# DeepReset2.net
KiCad netlist of a schematic drawn in EAGLE
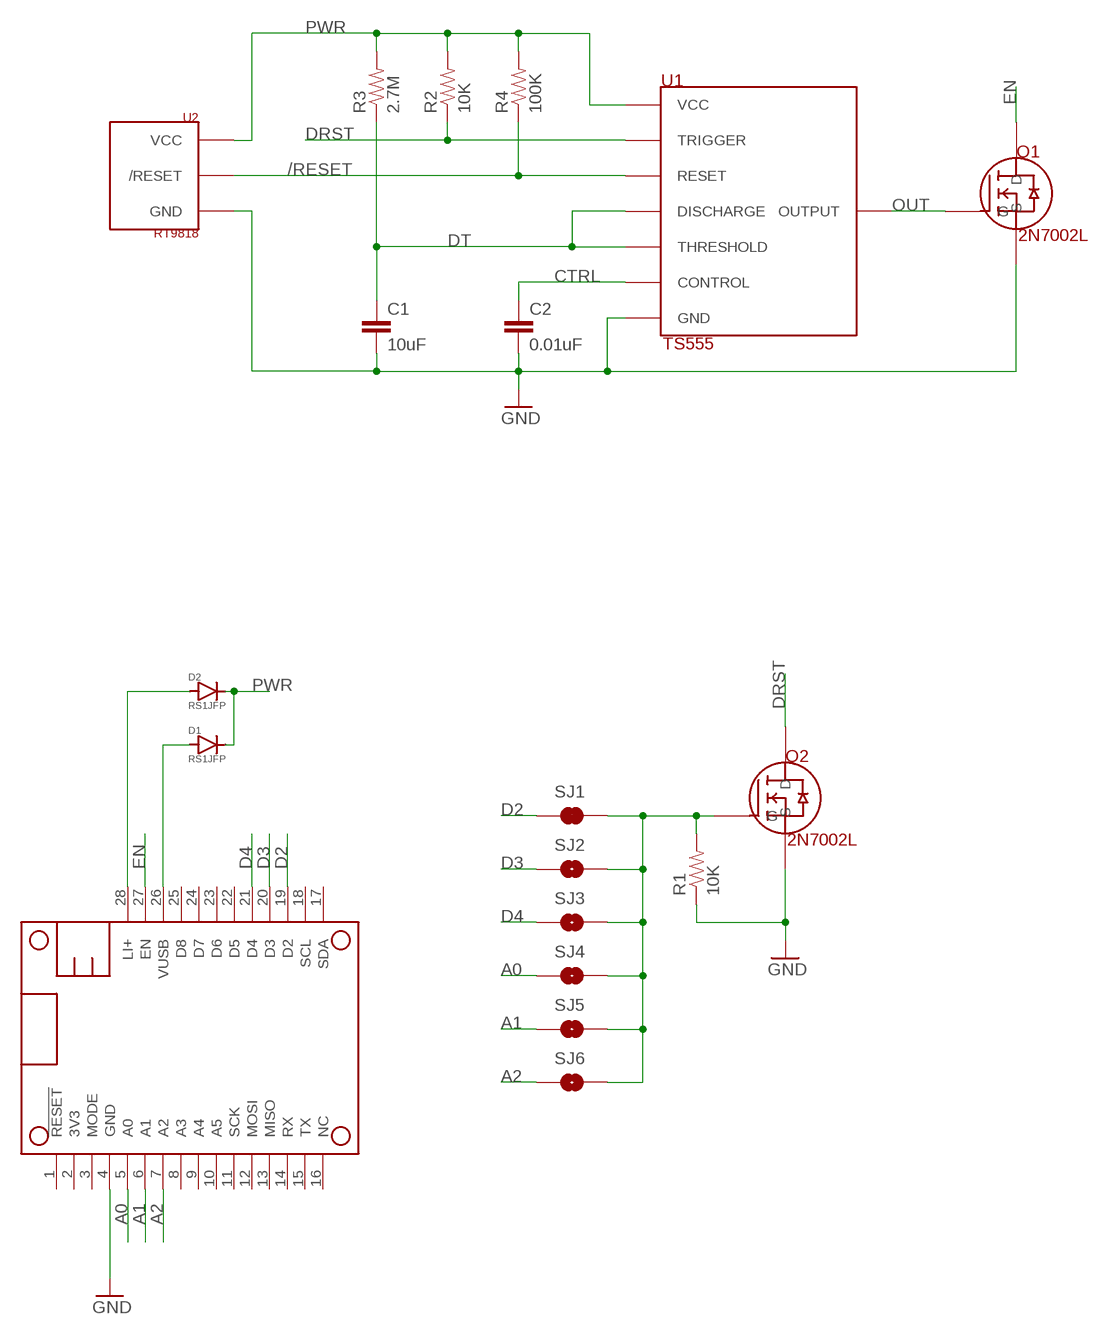
[diagram p0: schematic, sheet 1]

(export (version "E")
  (design (tool "Eeschema 10.0.6"))
  (components
    (comp (ref "C1")
      (value "10uF")
      (footprint "eagle-import:0603-CAP")
      (libsource (lib "eagle-import") (part "CAP-10UF-0603"))
    )
    (comp (ref "C2")
      (value "0.01uF")
      (footprint "eagle-import:0603-CAP")
      (libsource (lib "eagle-import") (part "CAP-0.01UF-0603"))
    )
    (comp (ref "D1")
      (value "RS1JFP")
      (footprint "eagle-import:SOD-123HE-ON")
      (libsource (lib "eagle-import") (part "DIODE-RS1JFP"))
    )
    (comp (ref "D2")
      (value "RS1JFP")
      (footprint "eagle-import:SOD-123HE-ON")
      (libsource (lib "eagle-import") (part "DIODE-RS1JFP"))
    )
    (comp (ref "MS1")
      (value "FEATHERWING_NODIM")
      (footprint "eagle-import:FEATHERWING_NODIM")
      (libsource (lib "eagle-import") (part "FEATHERWING_NODIM"))
    )
    (comp (ref "Q1")
      (value "2N7002L")
      (footprint "eagle-import:2N7002L")
      (libsource (lib "eagle-import") (part "2N7002L"))
    )
    (comp (ref "Q2")
      (value "2N7002L")
      (footprint "eagle-import:2N7002L")
      (libsource (lib "eagle-import") (part "2N7002L"))
    )
    (comp (ref "R1")
      (value "10K")
      (footprint "eagle-import:0603-RES")
      (libsource (lib "eagle-import") (part "RES-10K-06030603"))
    )
    (comp (ref "R2")
      (value "10K")
      (footprint "eagle-import:0603-RES")
      (libsource (lib "eagle-import") (part "RES-10K-06030603"))
    )
    (comp (ref "R3")
      (value "2.7M")
      (footprint "eagle-import:0603-RES")
      (libsource (lib "eagle-import") (part "RES-2.7M-0603"))
    )
    (comp (ref "R4")
      (value "100K")
      (footprint "eagle-import:0603-RES")
      (libsource (lib "eagle-import") (part "RES-100K-0603"))
    )
    (comp (ref "SJ1")
      (value "JUMPER-PAD-2-NC_BY_TRACENO_SILK")
      (footprint "eagle-import:PAD-JUMPER-2-NC_BY_TRACE_NO_SILK")
      (libsource (lib "eagle-import") (part "JUMPER-PAD-2-NC_BY_TRACENO_SILK"))
    )
    (comp (ref "SJ2")
      (value "JUMPER-PAD-2-NO")
      (footprint "eagle-import:PAD-JUMPER-2-NO_NO_SILK")
      (libsource (lib "eagle-import") (part "JUMPER-PAD-2-NO"))
    )
    (comp (ref "SJ3")
      (value "JUMPER-PAD-2-NO")
      (footprint "eagle-import:PAD-JUMPER-2-NO_NO_SILK")
      (libsource (lib "eagle-import") (part "JUMPER-PAD-2-NO"))
    )
    (comp (ref "SJ4")
      (value "JUMPER-PAD-2-NO")
      (footprint "eagle-import:PAD-JUMPER-2-NO_NO_SILK")
      (libsource (lib "eagle-import") (part "JUMPER-PAD-2-NO"))
    )
    (comp (ref "SJ5")
      (value "JUMPER-PAD-2-NO")
      (footprint "eagle-import:PAD-JUMPER-2-NO_NO_SILK")
      (libsource (lib "eagle-import") (part "JUMPER-PAD-2-NO"))
    )
    (comp (ref "SJ6")
      (value "JUMPER-PAD-2-NO")
      (footprint "eagle-import:PAD-JUMPER-2-NO_NO_SILK")
      (libsource (lib "eagle-import") (part "JUMPER-PAD-2-NO"))
    )
    (comp (ref "U1")
      (value "TS555")
      (footprint "eagle-import:8-SOIC-MICROCHIP-3.9")
      (libsource (lib "eagle-import") (part "TS555"))
    )
    (comp (ref "U2")
      (value "RT9818")
      (footprint "eagle-import:SOT-23-3")
      (libsource (lib "eagle-import") (part "RT9818"))
    )
  )
  (nets
    (net (code "1") (name "/3V3") (class "Default")
      (node (ref "MS1") (pin "2") (pinfunction "3V3_2") (pintype "power_in"))
    )
    (net (code "2") (name "/A0") (class "Default")
      (node (ref "MS1") (pin "5") (pinfunction "A0_5") (pintype "bidirectional"))
      (node (ref "SJ4") (pin "1") (pinfunction "1_1") (pintype "passive"))
    )
    (net (code "3") (name "/A1") (class "Default")
      (node (ref "MS1") (pin "6") (pinfunction "A1_6") (pintype "bidirectional"))
      (node (ref "SJ5") (pin "1") (pinfunction "1_1") (pintype "passive"))
    )
    (net (code "4") (name "/A2") (class "Default")
      (node (ref "MS1") (pin "7") (pinfunction "A2_7") (pintype "bidirectional"))
      (node (ref "SJ6") (pin "1") (pinfunction "1_1") (pintype "passive"))
    )
    (net (code "5") (name "/CTRL") (class "Default")
      (node (ref "C2") (pin "1") (pinfunction "1_1") (pintype "passive"))
      (node (ref "U1") (pin "5") (pinfunction "CONTROL_5") (pintype "bidirectional"))
    )
    (net (code "6") (name "/D2") (class "Default")
      (node (ref "MS1") (pin "19") (pinfunction "D2_19") (pintype "bidirectional"))
      (node (ref "SJ1") (pin "1") (pinfunction "1_1") (pintype "passive"))
    )
    (net (code "7") (name "/D3") (class "Default")
      (node (ref "MS1") (pin "20") (pinfunction "D3_20") (pintype "bidirectional"))
      (node (ref "SJ2") (pin "1") (pinfunction "1_1") (pintype "passive"))
    )
    (net (code "8") (name "/D4") (class "Default")
      (node (ref "MS1") (pin "21") (pinfunction "D4_21") (pintype "bidirectional"))
      (node (ref "SJ3") (pin "1") (pinfunction "1_1") (pintype "passive"))
    )
    (net (code "9") (name "/DRST") (class "Default")
      (node (ref "Q2") (pin "3") (pinfunction "D_3") (pintype "bidirectional"))
      (node (ref "R2") (pin "1") (pinfunction "1_1") (pintype "passive"))
      (node (ref "U1") (pin "2") (pinfunction "TRIGGER_2") (pintype "input"))
    )
    (net (code "10") (name "/DT") (class "Default")
      (node (ref "C1") (pin "1") (pinfunction "1_1") (pintype "passive"))
      (node (ref "R3") (pin "1") (pinfunction "1_1") (pintype "passive"))
      (node (ref "U1") (pin "6") (pinfunction "THRESHOLD_6") (pintype "bidirectional"))
      (node (ref "U1") (pin "7") (pinfunction "DISCHARGE_7") (pintype "bidirectional"))
    )
    (net (code "11") (name "/EN") (class "Default")
      (node (ref "MS1") (pin "27") (pinfunction "EN_27") (pintype "passive"))
      (node (ref "Q1") (pin "3") (pinfunction "D_3") (pintype "bidirectional"))
    )
    (net (code "12") (name "/OUT") (class "Default")
      (node (ref "Q1") (pin "1") (pinfunction "G_1") (pintype "bidirectional"))
      (node (ref "U1") (pin "3") (pinfunction "OUTPUT_3") (pintype "output"))
    )
    (net (code "13") (name "/PWR") (class "Default")
      (node (ref "D1") (pin "1") (pinfunction "CATHODE_1") (pintype "bidirectional"))
      (node (ref "D2") (pin "1") (pinfunction "CATHODE_1") (pintype "bidirectional"))
      (node (ref "R2") (pin "2") (pinfunction "2_2") (pintype "passive"))
      (node (ref "R3") (pin "2") (pinfunction "2_2") (pintype "passive"))
      (node (ref "R4") (pin "2") (pinfunction "2_2") (pintype "passive"))
      (node (ref "U1") (pin "8") (pinfunction "VCC_8") (pintype "power_in"))
      (node (ref "U2") (pin "3") (pinfunction "VCC_3") (pintype "power_in"))
    )
    (net (code "14") (name "/{slash}RESET") (class "Default")
      (node (ref "R4") (pin "1") (pinfunction "1_1") (pintype "passive"))
      (node (ref "U1") (pin "4") (pinfunction "RESET_4") (pintype "input"))
      (node (ref "U2") (pin "1") (pinfunction "/RESET_1") (pintype "output"))
    )
    (net (code "15") (name "GND") (class "Default")
      (node (ref "C1") (pin "2") (pinfunction "2_2") (pintype "passive"))
      (node (ref "C2") (pin "2") (pinfunction "2_2") (pintype "passive"))
      (node (ref "MS1") (pin "4") (pinfunction "GND_4") (pintype "power_in"))
      (node (ref "Q1") (pin "2") (pinfunction "S_2") (pintype "bidirectional"))
      (node (ref "Q2") (pin "2") (pinfunction "S_2") (pintype "bidirectional"))
      (node (ref "R1") (pin "1") (pinfunction "1_1") (pintype "passive"))
      (node (ref "U1") (pin "1") (pinfunction "GND_1") (pintype "power_in"))
      (node (ref "U2") (pin "2") (pinfunction "GND_2") (pintype "power_in"))
    )
    (net (code "16") (name "Net-(D1-ANODE)") (class "Default")
      (node (ref "D1") (pin "2") (pinfunction "ANODE_2") (pintype "bidirectional"))
      (node (ref "MS1") (pin "26") (pinfunction "VUSB_26") (pintype "power_in"))
    )
    (net (code "17") (name "Net-(D2-ANODE)") (class "Default")
      (node (ref "D2") (pin "2") (pinfunction "ANODE_2") (pintype "bidirectional"))
      (node (ref "MS1") (pin "28") (pinfunction "LI+_28") (pintype "power_in"))
    )
    (net (code "18") (name "Net-(Q2-G)") (class "Default")
      (node (ref "Q2") (pin "1") (pinfunction "G_1") (pintype "bidirectional"))
      (node (ref "R1") (pin "2") (pinfunction "2_2") (pintype "passive"))
      (node (ref "SJ1") (pin "2") (pinfunction "2_2") (pintype "passive"))
      (node (ref "SJ2") (pin "2") (pinfunction "2_2") (pintype "passive"))
      (node (ref "SJ3") (pin "2") (pinfunction "2_2") (pintype "passive"))
      (node (ref "SJ4") (pin "2") (pinfunction "2_2") (pintype "passive"))
      (node (ref "SJ5") (pin "2") (pinfunction "2_2") (pintype "passive"))
      (node (ref "SJ6") (pin "2") (pinfunction "2_2") (pintype "passive"))
    )
    (net (code "19") (name "unconnected-(MS1-A3-Pad8)") (class "Default")
      (node (ref "MS1") (pin "8") (pinfunction "A3_8") (pintype "bidirectional"))
    )
    (net (code "20") (name "unconnected-(MS1-A4-Pad9)") (class "Default")
      (node (ref "MS1") (pin "9") (pinfunction "A4_9") (pintype "bidirectional"))
    )
    (net (code "21") (name "unconnected-(MS1-A5-Pad10)") (class "Default")
      (node (ref "MS1") (pin "10") (pinfunction "A5_10") (pintype "bidirectional"))
    )
    (net (code "22") (name "unconnected-(MS1-D5-Pad22)") (class "Default")
      (node (ref "MS1") (pin "22") (pinfunction "D5_22") (pintype "bidirectional"))
    )
    (net (code "23") (name "unconnected-(MS1-D6-Pad23)") (class "Default")
      (node (ref "MS1") (pin "23") (pinfunction "D6_23") (pintype "bidirectional"))
    )
    (net (code "24") (name "unconnected-(MS1-D7-Pad24)") (class "Default")
      (node (ref "MS1") (pin "24") (pinfunction "D7_24") (pintype "bidirectional"))
    )
    (net (code "25") (name "unconnected-(MS1-D8-Pad25)") (class "Default")
      (node (ref "MS1") (pin "25") (pinfunction "D8_25") (pintype "bidirectional"))
    )
    (net (code "26") (name "unconnected-(MS1-MISO-Pad13)") (class "Default")
      (node (ref "MS1") (pin "13") (pinfunction "MISO_13") (pintype "bidirectional"))
    )
    (net (code "27") (name "unconnected-(MS1-MODE-Pad3)") (class "Default")
      (node (ref "MS1") (pin "3") (pinfunction "MODE_3") (pintype "passive"))
    )
    (net (code "28") (name "unconnected-(MS1-MOSI-Pad12)") (class "Default")
      (node (ref "MS1") (pin "12") (pinfunction "MOSI_12") (pintype "bidirectional"))
    )
    (net (code "29") (name "unconnected-(MS1-NC-Pad16)") (class "Default")
      (node (ref "MS1") (pin "16") (pinfunction "NC_16") (pintype "passive"))
    )
    (net (code "30") (name "unconnected-(MS1-RX-Pad14)") (class "Default")
      (node (ref "MS1") (pin "14") (pinfunction "RX_14") (pintype "bidirectional"))
    )
    (net (code "31") (name "unconnected-(MS1-SCK-Pad11)") (class "Default")
      (node (ref "MS1") (pin "11") (pinfunction "SCK_11") (pintype "bidirectional"))
    )
    (net (code "32") (name "unconnected-(MS1-SCL-Pad18)") (class "Default")
      (node (ref "MS1") (pin "18") (pinfunction "SCL_18") (pintype "bidirectional"))
    )
    (net (code "33") (name "unconnected-(MS1-SDA-Pad17)") (class "Default")
      (node (ref "MS1") (pin "17") (pinfunction "SDA_17") (pintype "bidirectional"))
    )
    (net (code "34") (name "unconnected-(MS1-TX-Pad15)") (class "Default")
      (node (ref "MS1") (pin "15") (pinfunction "TX_15") (pintype "bidirectional"))
    )
    (net (code "35") (name "unconnected-(MS1-~{RESET}-Pad1)") (class "Default")
      (node (ref "MS1") (pin "1") (pinfunction "~{RESET}_1") (pintype "input"))
    )
  )
)
